# CFD.net
KiCad netlist of a schematic drawn in Altium Designer
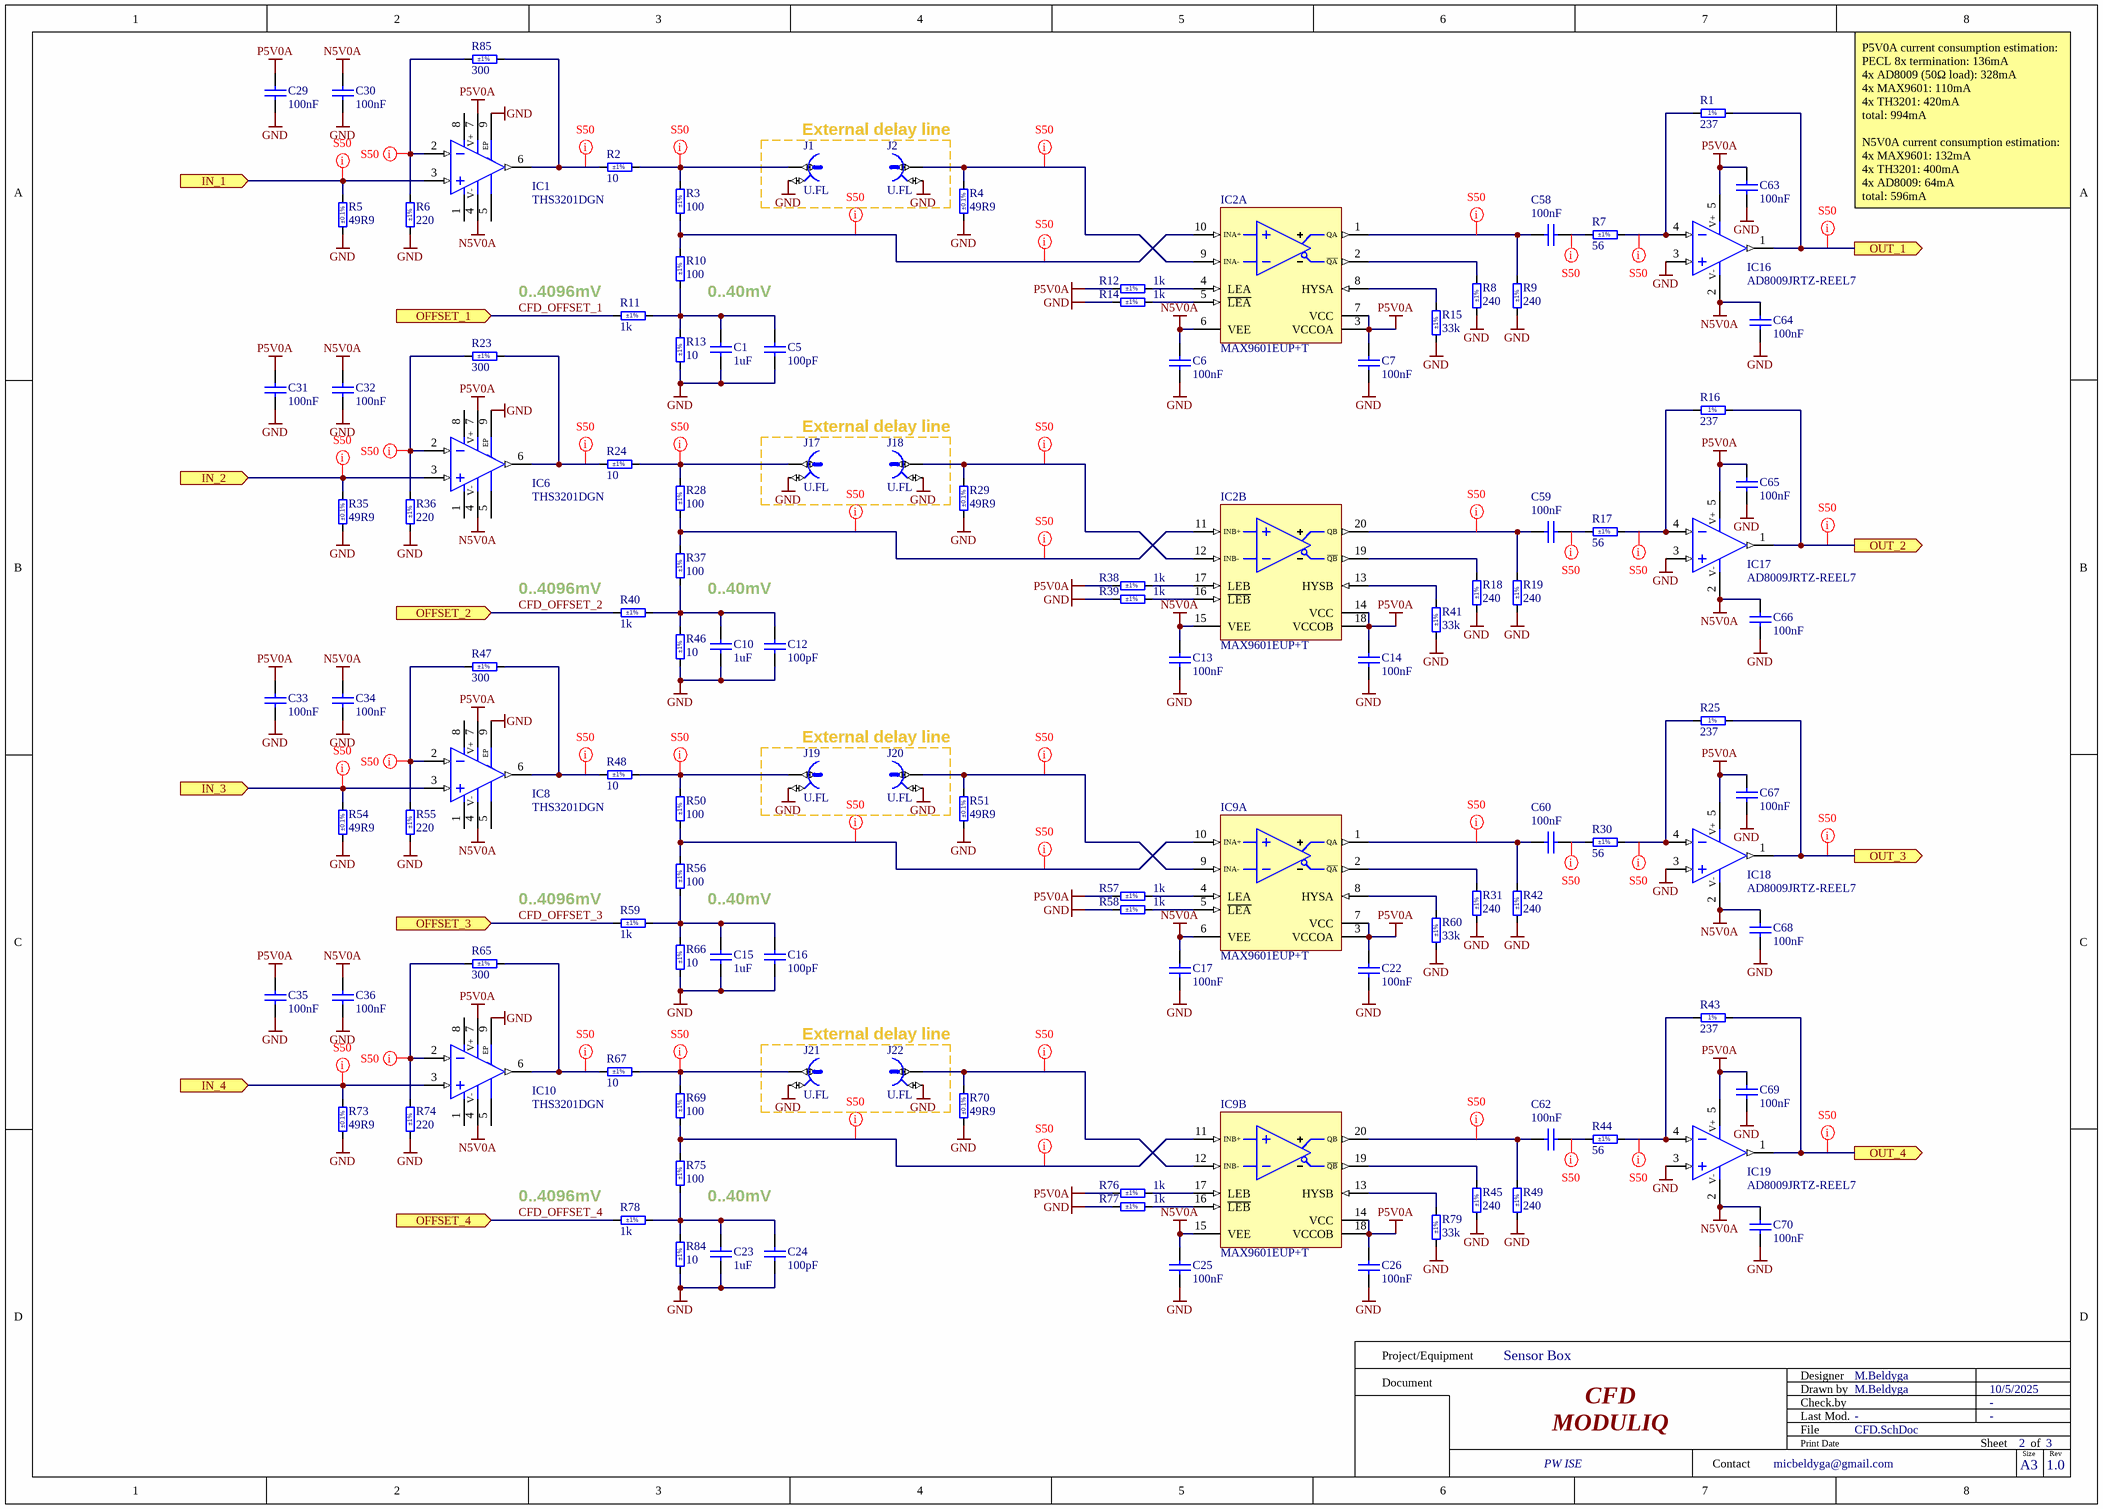
[diagram p0: CFD.SchDoc]

(export (version "E")
  (design (tool "Eeschema 10.0.6"))
  (components
    (comp (ref "C1")
      (value "1uF")
      (footprint "CAPC1005X55N")
      (description "Non-polarised capacitor")
      (fields
        (field (name "PART NUMBER") "CC0402_1UF_16V_10%_X5R")
        (field (name "VOLTAGE") "16V")
        (field (name "AUTHOR") "CERN DEM JLC")
      )
      (libsource (lib "Capacitors") (part "Capacitor - non polarized"))
    )
    (comp (ref "C5")
      (value "100pF")
      (footprint "CAPC1005X55N")
      (description "Non-polarised capacitor")
      (fields
        (field (name "PART NUMBER") "CC0402_100PF_25V_1%_C0G")
        (field (name "VOLTAGE") "25V")
        (field (name "AUTHOR") "CERN DEM HF")
      )
      (libsource (lib "Capacitors") (part "Capacitor - non polarized"))
    )
    (comp (ref "C6")
      (value "100nF")
      (footprint "CAPC1005X55N")
      (description "Non-polarised capacitor")
      (fields
        (field (name "PART NUMBER") "CC0402_100NF_50V_10%_X7R")
        (field (name "VOLTAGE") "50V")
        (field (name "AUTHOR") "CERN DEM MR")
      )
      (libsource (lib "Capacitors") (part "Capacitor - non polarized"))
    )
    (comp (ref "C7")
      (value "100nF")
      (footprint "CAPC1005X55N")
      (description "Non-polarised capacitor")
      (fields
        (field (name "PART NUMBER") "CC0402_100NF_50V_10%_X7R")
        (field (name "VOLTAGE") "50V")
        (field (name "AUTHOR") "CERN DEM MR")
      )
      (libsource (lib "Capacitors") (part "Capacitor - non polarized"))
    )
    (comp (ref "C10")
      (value "1uF")
      (footprint "CAPC1005X55N")
      (description "Non-polarised capacitor")
      (fields
        (field (name "PART NUMBER") "CC0402_1UF_16V_10%_X5R")
        (field (name "VOLTAGE") "16V")
        (field (name "AUTHOR") "CERN DEM JLC")
      )
      (libsource (lib "Capacitors") (part "Capacitor - non polarized"))
    )
    (comp (ref "C12")
      (value "100pF")
      (footprint "CAPC1005X55N")
      (description "Non-polarised capacitor")
      (fields
        (field (name "PART NUMBER") "CC0402_100PF_25V_1%_C0G")
        (field (name "VOLTAGE") "25V")
        (field (name "AUTHOR") "CERN DEM HF")
      )
      (libsource (lib "Capacitors") (part "Capacitor - non polarized"))
    )
    (comp (ref "C13")
      (value "100nF")
      (footprint "CAPC1005X55N")
      (description "Non-polarised capacitor")
      (fields
        (field (name "PART NUMBER") "CC0402_100NF_50V_10%_X7R")
        (field (name "VOLTAGE") "50V")
        (field (name "AUTHOR") "CERN DEM MR")
      )
      (libsource (lib "Capacitors") (part "Capacitor - non polarized"))
    )
    (comp (ref "C14")
      (value "100nF")
      (footprint "CAPC1005X55N")
      (description "Non-polarised capacitor")
      (fields
        (field (name "PART NUMBER") "CC0402_100NF_50V_10%_X7R")
        (field (name "VOLTAGE") "50V")
        (field (name "AUTHOR") "CERN DEM MR")
      )
      (libsource (lib "Capacitors") (part "Capacitor - non polarized"))
    )
    (comp (ref "C15")
      (value "1uF")
      (footprint "CAPC1005X55N")
      (description "Non-polarised capacitor")
      (fields
        (field (name "PART NUMBER") "CC0402_1UF_16V_10%_X5R")
        (field (name "VOLTAGE") "16V")
        (field (name "AUTHOR") "CERN DEM JLC")
      )
      (libsource (lib "Capacitors") (part "Capacitor - non polarized"))
    )
    (comp (ref "C16")
      (value "100pF")
      (footprint "CAPC1005X55N")
      (description "Non-polarised capacitor")
      (fields
        (field (name "PART NUMBER") "CC0402_100PF_25V_1%_C0G")
        (field (name "VOLTAGE") "25V")
        (field (name "AUTHOR") "CERN DEM HF")
      )
      (libsource (lib "Capacitors") (part "Capacitor - non polarized"))
    )
    (comp (ref "C17")
      (value "100nF")
      (footprint "CAPC1005X55N")
      (description "Non-polarised capacitor")
      (fields
        (field (name "PART NUMBER") "CC0402_100NF_50V_10%_X7R")
        (field (name "VOLTAGE") "50V")
        (field (name "AUTHOR") "CERN DEM MR")
      )
      (libsource (lib "Capacitors") (part "Capacitor - non polarized"))
    )
    (comp (ref "C22")
      (value "100nF")
      (footprint "CAPC1005X55N")
      (description "Non-polarised capacitor")
      (fields
        (field (name "PART NUMBER") "CC0402_100NF_50V_10%_X7R")
        (field (name "VOLTAGE") "50V")
        (field (name "AUTHOR") "CERN DEM MR")
      )
      (libsource (lib "Capacitors") (part "Capacitor - non polarized"))
    )
    (comp (ref "C23")
      (value "1uF")
      (footprint "CAPC1005X55N")
      (description "Non-polarised capacitor")
      (fields
        (field (name "PART NUMBER") "CC0402_1UF_16V_10%_X5R")
        (field (name "VOLTAGE") "16V")
        (field (name "AUTHOR") "CERN DEM JLC")
      )
      (libsource (lib "Capacitors") (part "Capacitor - non polarized"))
    )
    (comp (ref "C24")
      (value "100pF")
      (footprint "CAPC1005X55N")
      (description "Non-polarised capacitor")
      (fields
        (field (name "PART NUMBER") "CC0402_100PF_25V_1%_C0G")
        (field (name "VOLTAGE") "25V")
        (field (name "AUTHOR") "CERN DEM HF")
      )
      (libsource (lib "Capacitors") (part "Capacitor - non polarized"))
    )
    (comp (ref "C25")
      (value "100nF")
      (footprint "CAPC1005X55N")
      (description "Non-polarised capacitor")
      (fields
        (field (name "PART NUMBER") "CC0402_100NF_50V_10%_X7R")
        (field (name "VOLTAGE") "50V")
        (field (name "AUTHOR") "CERN DEM MR")
      )
      (libsource (lib "Capacitors") (part "Capacitor - non polarized"))
    )
    (comp (ref "C26")
      (value "100nF")
      (footprint "CAPC1005X55N")
      (description "Non-polarised capacitor")
      (fields
        (field (name "PART NUMBER") "CC0402_100NF_50V_10%_X7R")
        (field (name "VOLTAGE") "50V")
        (field (name "AUTHOR") "CERN DEM MR")
      )
      (libsource (lib "Capacitors") (part "Capacitor - non polarized"))
    )
    (comp (ref "C29")
      (value "100nF")
      (footprint "CAPC1005X55N")
      (description "Non-polarised capacitor")
      (fields
        (field (name "PART NUMBER") "CC0402_100NF_50V_10%_X7R")
        (field (name "VOLTAGE") "50V")
        (field (name "AUTHOR") "CERN DEM MR")
      )
      (libsource (lib "Capacitors") (part "Capacitor - non polarized"))
    )
    (comp (ref "C30")
      (value "100nF")
      (footprint "CAPC1005X55N")
      (description "Non-polarised capacitor")
      (fields
        (field (name "PART NUMBER") "CC0402_100NF_50V_10%_X7R")
        (field (name "VOLTAGE") "50V")
        (field (name "AUTHOR") "CERN DEM MR")
      )
      (libsource (lib "Capacitors") (part "Capacitor - non polarized"))
    )
    (comp (ref "C31")
      (value "100nF")
      (footprint "CAPC1005X55N")
      (description "Non-polarised capacitor")
      (fields
        (field (name "PART NUMBER") "CC0402_100NF_50V_10%_X7R")
        (field (name "VOLTAGE") "50V")
        (field (name "AUTHOR") "CERN DEM MR")
      )
      (libsource (lib "Capacitors") (part "Capacitor - non polarized"))
    )
    (comp (ref "C32")
      (value "100nF")
      (footprint "CAPC1005X55N")
      (description "Non-polarised capacitor")
      (fields
        (field (name "PART NUMBER") "CC0402_100NF_50V_10%_X7R")
        (field (name "VOLTAGE") "50V")
        (field (name "AUTHOR") "CERN DEM MR")
      )
      (libsource (lib "Capacitors") (part "Capacitor - non polarized"))
    )
    (comp (ref "C33")
      (value "100nF")
      (footprint "CAPC1005X55N")
      (description "Non-polarised capacitor")
      (fields
        (field (name "PART NUMBER") "CC0402_100NF_50V_10%_X7R")
        (field (name "VOLTAGE") "50V")
        (field (name "AUTHOR") "CERN DEM MR")
      )
      (libsource (lib "Capacitors") (part "Capacitor - non polarized"))
    )
    (comp (ref "C34")
      (value "100nF")
      (footprint "CAPC1005X55N")
      (description "Non-polarised capacitor")
      (fields
        (field (name "PART NUMBER") "CC0402_100NF_50V_10%_X7R")
        (field (name "VOLTAGE") "50V")
        (field (name "AUTHOR") "CERN DEM MR")
      )
      (libsource (lib "Capacitors") (part "Capacitor - non polarized"))
    )
    (comp (ref "C35")
      (value "100nF")
      (footprint "CAPC1005X55N")
      (description "Non-polarised capacitor")
      (fields
        (field (name "PART NUMBER") "CC0402_100NF_50V_10%_X7R")
        (field (name "VOLTAGE") "50V")
        (field (name "AUTHOR") "CERN DEM MR")
      )
      (libsource (lib "Capacitors") (part "Capacitor - non polarized"))
    )
    (comp (ref "C36")
      (value "100nF")
      (footprint "CAPC1005X55N")
      (description "Non-polarised capacitor")
      (fields
        (field (name "PART NUMBER") "CC0402_100NF_50V_10%_X7R")
        (field (name "VOLTAGE") "50V")
        (field (name "AUTHOR") "CERN DEM MR")
      )
      (libsource (lib "Capacitors") (part "Capacitor - non polarized"))
    )
    (comp (ref "C58")
      (value "100nF")
      (footprint "CAPC1005X55N")
      (description "Non-polarised capacitor")
      (fields
        (field (name "PART NUMBER") "CC0402_100NF_50V_10%_X7R")
        (field (name "VOLTAGE") "50V")
        (field (name "AUTHOR") "CERN DEM MR")
      )
      (libsource (lib "Capacitors") (part "Capacitor - non polarized"))
    )
    (comp (ref "C59")
      (value "100nF")
      (footprint "CAPC1005X55N")
      (description "Non-polarised capacitor")
      (fields
        (field (name "PART NUMBER") "CC0402_100NF_50V_10%_X7R")
        (field (name "VOLTAGE") "50V")
        (field (name "AUTHOR") "CERN DEM MR")
      )
      (libsource (lib "Capacitors") (part "Capacitor - non polarized"))
    )
    (comp (ref "C60")
      (value "100nF")
      (footprint "CAPC1005X55N")
      (description "Non-polarised capacitor")
      (fields
        (field (name "PART NUMBER") "CC0402_100NF_50V_10%_X7R")
        (field (name "VOLTAGE") "50V")
        (field (name "AUTHOR") "CERN DEM MR")
      )
      (libsource (lib "Capacitors") (part "Capacitor - non polarized"))
    )
    (comp (ref "C62")
      (value "100nF")
      (footprint "CAPC1005X55N")
      (description "Non-polarised capacitor")
      (fields
        (field (name "PART NUMBER") "CC0402_100NF_50V_10%_X7R")
        (field (name "VOLTAGE") "50V")
        (field (name "AUTHOR") "CERN DEM MR")
      )
      (libsource (lib "Capacitors") (part "Capacitor - non polarized"))
    )
    (comp (ref "C63")
      (value "100nF")
      (footprint "CAPC1005X55N")
      (description "Non-polarised capacitor")
      (fields
        (field (name "PART NUMBER") "CC0402_100NF_50V_10%_X7R")
        (field (name "VOLTAGE") "50V")
        (field (name "AUTHOR") "CERN DEM MR")
      )
      (libsource (lib "Capacitors") (part "Capacitor - non polarized"))
    )
    (comp (ref "C64")
      (value "100nF")
      (footprint "CAPC1005X55N")
      (description "Non-polarised capacitor")
      (fields
        (field (name "PART NUMBER") "CC0402_100NF_50V_10%_X7R")
        (field (name "VOLTAGE") "50V")
        (field (name "AUTHOR") "CERN DEM MR")
      )
      (libsource (lib "Capacitors") (part "Capacitor - non polarized"))
    )
    (comp (ref "C65")
      (value "100nF")
      (footprint "CAPC1005X55N")
      (description "Non-polarised capacitor")
      (fields
        (field (name "PART NUMBER") "CC0402_100NF_50V_10%_X7R")
        (field (name "VOLTAGE") "50V")
        (field (name "AUTHOR") "CERN DEM MR")
      )
      (libsource (lib "Capacitors") (part "Capacitor - non polarized"))
    )
    (comp (ref "C66")
      (value "100nF")
      (footprint "CAPC1005X55N")
      (description "Non-polarised capacitor")
      (fields
        (field (name "PART NUMBER") "CC0402_100NF_50V_10%_X7R")
        (field (name "VOLTAGE") "50V")
        (field (name "AUTHOR") "CERN DEM MR")
      )
      (libsource (lib "Capacitors") (part "Capacitor - non polarized"))
    )
    (comp (ref "C67")
      (value "100nF")
      (footprint "CAPC1005X55N")
      (description "Non-polarised capacitor")
      (fields
        (field (name "PART NUMBER") "CC0402_100NF_50V_10%_X7R")
        (field (name "VOLTAGE") "50V")
        (field (name "AUTHOR") "CERN DEM MR")
      )
      (libsource (lib "Capacitors") (part "Capacitor - non polarized"))
    )
    (comp (ref "C68")
      (value "100nF")
      (footprint "CAPC1005X55N")
      (description "Non-polarised capacitor")
      (fields
        (field (name "PART NUMBER") "CC0402_100NF_50V_10%_X7R")
        (field (name "VOLTAGE") "50V")
        (field (name "AUTHOR") "CERN DEM MR")
      )
      (libsource (lib "Capacitors") (part "Capacitor - non polarized"))
    )
    (comp (ref "C69")
      (value "100nF")
      (footprint "CAPC1005X55N")
      (description "Non-polarised capacitor")
      (fields
        (field (name "PART NUMBER") "CC0402_100NF_50V_10%_X7R")
        (field (name "VOLTAGE") "50V")
        (field (name "AUTHOR") "CERN DEM MR")
      )
      (libsource (lib "Capacitors") (part "Capacitor - non polarized"))
    )
    (comp (ref "C70")
      (value "100nF")
      (footprint "CAPC1005X55N")
      (description "Non-polarised capacitor")
      (fields
        (field (name "PART NUMBER") "CC0402_100NF_50V_10%_X7R")
        (field (name "VOLTAGE") "50V")
        (field (name "AUTHOR") "CERN DEM MR")
      )
      (libsource (lib "Capacitors") (part "Capacitor - non polarized"))
    )
    (comp (ref "IC1")
      (value "THS3201DGN")
      (footprint "SOP65P490X110-9N-R152X190")
      (description "Operational Amplifier with Exposed Thermal Pad")
      (fields (field (name "MANUFACTURER") "TEXAS INSTRUMENTS") (field (name "AUTHOR") "CERN DEM JLC"))
      (libsource (lib "ICs And Semiconductors") (part "Operational Amplifier Type5 + Exposed Pad"))
    )
    (comp (ref "IC2")
      (value "MAX9601EUP+T")
      (footprint "SOP65P640X120-20N")
      (description "Dual ECL and Dual/Quad PECL, 500ps, Ultra-High-Speed Comparators")
      (fields (field (name "MANUFACTURER") "Analog Devices"))
      (libsource (lib "mb") (part "MAX9601EUP+T"))
    )
    (comp (ref "IC6")
      (value "THS3201DGN")
      (footprint "SOP65P490X110-9N-R152X190")
      (description "Operational Amplifier with Exposed Thermal Pad")
      (fields (field (name "MANUFACTURER") "TEXAS INSTRUMENTS") (field (name "AUTHOR") "CERN DEM JLC"))
      (libsource (lib "ICs And Semiconductors") (part "Operational Amplifier Type5 + Exposed Pad"))
    )
    (comp (ref "IC8")
      (value "THS3201DGN")
      (footprint "SOP65P490X110-9N-R152X190")
      (description "Operational Amplifier with Exposed Thermal Pad")
      (fields (field (name "MANUFACTURER") "TEXAS INSTRUMENTS") (field (name "AUTHOR") "CERN DEM JLC"))
      (libsource (lib "ICs And Semiconductors") (part "Operational Amplifier Type5 + Exposed Pad"))
    )
    (comp (ref "IC9")
      (value "MAX9601EUP+T")
      (footprint "SOP65P640X120-20N")
      (description "Dual ECL and Dual/Quad PECL, 500ps, Ultra-High-Speed Comparators")
      (fields (field (name "MANUFACTURER") "Analog Devices"))
      (libsource (lib "mb") (part "MAX9601EUP+T"))
    )
    (comp (ref "IC10")
      (value "THS3201DGN")
      (footprint "SOP65P490X110-9N-R152X190")
      (description "Operational Amplifier with Exposed Thermal Pad")
      (fields (field (name "MANUFACTURER") "TEXAS INSTRUMENTS") (field (name "AUTHOR") "CERN DEM JLC"))
      (libsource (lib "ICs And Semiconductors") (part "Operational Amplifier Type5 + Exposed Pad"))
    )
    (comp (ref "IC16")
      (value "AD8009JRTZ-REEL7")
      (footprint "SOT95P280X145-5N")
      (description "Operational Amplifier")
      (fields
        (field (name "MANUFACTURER") "ANALOG DEVICES")
        (field (name "MANUFACTURER PART NUMBER") "AD8009JRT")
        (field (name "AUTHOR") "CERN DEM JLC")
      )
      (libsource (lib "ICs And Semiconductors") (part "Operational Amplifier Type7"))
    )
    (comp (ref "IC17")
      (value "AD8009JRTZ-REEL7")
      (footprint "SOT95P280X145-5N")
      (description "Operational Amplifier")
      (fields
        (field (name "MANUFACTURER") "ANALOG DEVICES")
        (field (name "MANUFACTURER PART NUMBER") "AD8009JRT")
        (field (name "AUTHOR") "CERN DEM JLC")
      )
      (libsource (lib "ICs And Semiconductors") (part "Operational Amplifier Type7"))
    )
    (comp (ref "IC18")
      (value "AD8009JRTZ-REEL7")
      (footprint "SOT95P280X145-5N")
      (description "Operational Amplifier")
      (fields
        (field (name "MANUFACTURER") "ANALOG DEVICES")
        (field (name "MANUFACTURER PART NUMBER") "AD8009JRT")
        (field (name "AUTHOR") "CERN DEM JLC")
      )
      (libsource (lib "ICs And Semiconductors") (part "Operational Amplifier Type7"))
    )
    (comp (ref "IC19")
      (value "AD8009JRTZ-REEL7")
      (footprint "SOT95P280X145-5N")
      (description "Operational Amplifier")
      (fields
        (field (name "MANUFACTURER") "ANALOG DEVICES")
        (field (name "MANUFACTURER PART NUMBER") "AD8009JRT")
        (field (name "AUTHOR") "CERN DEM JLC")
      )
      (libsource (lib "ICs And Semiconductors") (part "Operational Amplifier Type7"))
    )
    (comp (ref "J1")
      (value "U.FL")
      (footprint "HIROSE_U.FL-R-SMT-1")
      (fields
        (field (name "PART NUMBER") "HIROSE_U.FL-R-SMT-1(10)")
        (field (name "MANUFACTURER") "HIROSE (HRS)")
        (field (name "MANUFACTURER PART NUMBER") "U.FL-R-SMT-1")
        (field (name "AUTHOR") "CERN DEM JLC")
      )
      (libsource (lib "") (part "Coax_1Male_1Shield_1"))
    )
    (comp (ref "J2")
      (value "U.FL")
      (footprint "HIROSE_U.FL-R-SMT-1")
      (fields
        (field (name "PART NUMBER") "HIROSE_U.FL-R-SMT-1(10)")
        (field (name "MANUFACTURER") "HIROSE (HRS)")
        (field (name "MANUFACTURER PART NUMBER") "U.FL-R-SMT-1")
        (field (name "AUTHOR") "CERN DEM JLC")
      )
      (libsource (lib "Connectors") (part "Coax_1Male_1Shield"))
    )
    (comp (ref "J17")
      (value "U.FL")
      (footprint "HIROSE_U.FL-R-SMT-1")
      (fields
        (field (name "PART NUMBER") "HIROSE_U.FL-R-SMT-1(10)")
        (field (name "MANUFACTURER") "HIROSE (HRS)")
        (field (name "MANUFACTURER PART NUMBER") "U.FL-R-SMT-1")
        (field (name "AUTHOR") "CERN DEM JLC")
      )
      (libsource (lib "") (part "Coax_1Male_1Shield_1"))
    )
    (comp (ref "J18")
      (value "U.FL")
      (footprint "HIROSE_U.FL-R-SMT-1")
      (fields
        (field (name "PART NUMBER") "HIROSE_U.FL-R-SMT-1(10)")
        (field (name "MANUFACTURER") "HIROSE (HRS)")
        (field (name "MANUFACTURER PART NUMBER") "U.FL-R-SMT-1")
        (field (name "AUTHOR") "CERN DEM JLC")
      )
      (libsource (lib "Connectors") (part "Coax_1Male_1Shield"))
    )
    (comp (ref "J19")
      (value "U.FL")
      (footprint "HIROSE_U.FL-R-SMT-1")
      (fields
        (field (name "PART NUMBER") "HIROSE_U.FL-R-SMT-1(10)")
        (field (name "MANUFACTURER") "HIROSE (HRS)")
        (field (name "MANUFACTURER PART NUMBER") "U.FL-R-SMT-1")
        (field (name "AUTHOR") "CERN DEM JLC")
      )
      (libsource (lib "") (part "Coax_1Male_1Shield_1"))
    )
    (comp (ref "J20")
      (value "U.FL")
      (footprint "HIROSE_U.FL-R-SMT-1")
      (fields
        (field (name "PART NUMBER") "HIROSE_U.FL-R-SMT-1(10)")
        (field (name "MANUFACTURER") "HIROSE (HRS)")
        (field (name "MANUFACTURER PART NUMBER") "U.FL-R-SMT-1")
        (field (name "AUTHOR") "CERN DEM JLC")
      )
      (libsource (lib "Connectors") (part "Coax_1Male_1Shield"))
    )
    (comp (ref "J21")
      (value "U.FL")
      (footprint "HIROSE_U.FL-R-SMT-1")
      (fields
        (field (name "PART NUMBER") "HIROSE_U.FL-R-SMT-1(10)")
        (field (name "MANUFACTURER") "HIROSE (HRS)")
        (field (name "MANUFACTURER PART NUMBER") "U.FL-R-SMT-1")
        (field (name "AUTHOR") "CERN DEM JLC")
      )
      (libsource (lib "") (part "Coax_1Male_1Shield_1"))
    )
    (comp (ref "J22")
      (value "U.FL")
      (footprint "HIROSE_U.FL-R-SMT-1")
      (fields
        (field (name "PART NUMBER") "HIROSE_U.FL-R-SMT-1(10)")
        (field (name "MANUFACTURER") "HIROSE (HRS)")
        (field (name "MANUFACTURER PART NUMBER") "U.FL-R-SMT-1")
        (field (name "AUTHOR") "CERN DEM JLC")
      )
      (libsource (lib "Connectors") (part "Coax_1Male_1Shield"))
    )
    (comp (ref "R1")
      (value "237")
      (footprint "RESC1005X40N")
      (description "RES 237 OHM 1% 1/16W 0402")
      (fields
        (field (name "PART NUMBER") "R0402_237R_1%_0.0625W")
        (field (name "POWER") "0.0625W")
        (field (name "AUTHOR") "Michal Beldyga")
      )
      (libsource (lib "") (part "Resistor - 1%_1"))
    )
    (comp (ref "R2")
      (value "10")
      (footprint "RESC1005X40N")
      (description "Resistor - 1%")
      (fields
        (field (name "TOLERANCE") "±1%")
        (field (name "PART NUMBER") "R0402_10R_1%_0.0625W_200PPM")
        (field (name "POWER") "0.0625W")
        (field (name "AUTHOR") "CERN DEM JLC")
      )
      (libsource (lib "Resistors") (part "Resistor - 1%"))
    )
    (comp (ref "R3")
      (value "100")
      (footprint "RESC1005X40N")
      (description "Resistor - 1%")
      (fields
        (field (name "TOLERANCE") "±1%")
        (field (name "PART NUMBER") "R0402_100R_1%_0.0625W_100PPM")
        (field (name "POWER") "0.0625W")
        (field (name "AUTHOR") "CERN DEM JLC")
      )
      (libsource (lib "Resistors") (part "Resistor - 1%"))
    )
    (comp (ref "R4")
      (value "49R9")
      (footprint "RESC2012X60N")
      (description "Resistor - 0.1%")
      (fields
        (field (name "TOLERANCE") "±0.1%")
        (field (name "PART NUMBER") "R0805_49R9_0.1%_0.1W_10PPM")
        (field (name "POWER") "0.1W")
        (field (name "AUTHOR") "CERN DEM JLC")
      )
      (libsource (lib "Resistors") (part "Resistor - 0.1%"))
    )
    (comp (ref "R5")
      (value "49R9")
      (footprint "RESC2012X60N")
      (description "Resistor - 0.1%")
      (fields
        (field (name "TOLERANCE") "±0.1%")
        (field (name "PART NUMBER") "R0805_49R9_0.1%_0.1W_10PPM")
        (field (name "POWER") "0.1W")
        (field (name "AUTHOR") "CERN DEM JLC")
      )
      (libsource (lib "Resistors") (part "Resistor - 0.1%"))
    )
    (comp (ref "R6")
      (value "220")
      (footprint "RESC1005X40N")
      (description "Resistor - 1%")
      (fields
        (field (name "TOLERANCE") "±1%")
        (field (name "PART NUMBER") "R0402_220R_1%_0.0625W_100PPM")
        (field (name "POWER") "0.0625W")
        (field (name "AUTHOR") "CERN DEM JLC")
      )
      (libsource (lib "Resistors") (part "Resistor - 1%"))
    )
    (comp (ref "R7")
      (value "56")
      (footprint "RESC1005X40N")
      (description "Resistor - 1%")
      (fields
        (field (name "TOLERANCE") "±1%")
        (field (name "PART NUMBER") "R0402_56R_1%_0.0625W_100PPM")
        (field (name "POWER") "0.0625W")
        (field (name "AUTHOR") "CERN DEM JLC")
      )
      (libsource (lib "Resistors") (part "Resistor - 1%"))
    )
    (comp (ref "R8")
      (value "240")
      (footprint "RESC1608X55N")
      (description "Resistor - 1%")
      (fields
        (field (name "TOLERANCE") "±1%")
        (field (name "PART NUMBER") "R0603_240R_1%_0.1W_100PPM")
        (field (name "POWER") "0.1W")
        (field (name "AUTHOR") "CERN DEM JLC")
      )
      (libsource (lib "Resistors") (part "Resistor - 1%"))
    )
    (comp (ref "R9")
      (value "240")
      (footprint "RESC1608X55N")
      (description "Resistor - 1%")
      (fields
        (field (name "TOLERANCE") "±1%")
        (field (name "PART NUMBER") "R0603_240R_1%_0.1W_100PPM")
        (field (name "POWER") "0.1W")
        (field (name "AUTHOR") "CERN DEM JLC")
      )
      (libsource (lib "Resistors") (part "Resistor - 1%"))
    )
    (comp (ref "R10")
      (value "100")
      (footprint "RESC1005X40N")
      (description "Resistor - 1%")
      (fields
        (field (name "TOLERANCE") "±1%")
        (field (name "PART NUMBER") "R0402_100R_1%_0.0625W_100PPM")
        (field (name "POWER") "0.0625W")
        (field (name "AUTHOR") "CERN DEM JLC")
      )
      (libsource (lib "Resistors") (part "Resistor - 1%"))
    )
    (comp (ref "R11")
      (value "1k")
      (footprint "RESC1005X40N")
      (description "Resistor - 1%")
      (fields
        (field (name "TOLERANCE") "±1%")
        (field (name "PART NUMBER") "R0402_1K_1%_0.0625W_100PPM")
        (field (name "POWER") "0.0625W")
        (field (name "AUTHOR") "CERN DEM JLC")
      )
      (libsource (lib "Resistors") (part "Resistor - 1%"))
    )
    (comp (ref "R12")
      (value "1k")
      (footprint "RESC1005X40N")
      (description "Resistor - 1%")
      (fields
        (field (name "TOLERANCE") "±1%")
        (field (name "PART NUMBER") "R0402_1K_1%_0.0625W_100PPM")
        (field (name "POWER") "0.0625W")
        (field (name "AUTHOR") "CERN DEM JLC")
      )
      (libsource (lib "Resistors") (part "Resistor - 1%"))
    )
    (comp (ref "R13")
      (value "10")
      (footprint "RESC1005X40N")
      (description "Resistor - 1%")
      (fields
        (field (name "TOLERANCE") "±1%")
        (field (name "PART NUMBER") "R0402_10R_1%_0.0625W_200PPM")
        (field (name "POWER") "0.0625W")
        (field (name "AUTHOR") "CERN DEM JLC")
      )
      (libsource (lib "Resistors") (part "Resistor - 1%"))
    )
    (comp (ref "R14")
      (value "1k")
      (footprint "RESC1005X40N")
      (description "Resistor - 1%")
      (fields
        (field (name "TOLERANCE") "±1%")
        (field (name "PART NUMBER") "R0402_1K_1%_0.0625W_100PPM")
        (field (name "POWER") "0.0625W")
        (field (name "AUTHOR") "CERN DEM JLC")
      )
      (libsource (lib "Resistors") (part "Resistor - 1%"))
    )
    (comp (ref "R15")
      (value "33k")
      (footprint "RESC1005X40N")
      (description "Resistor - 1%")
      (fields
        (field (name "TOLERANCE") "±1%")
        (field (name "PART NUMBER") "R0402_33K_1%_0.0625W_100PPM")
        (field (name "POWER") "0.0625W")
        (field (name "AUTHOR") "CERN DEM JLC")
      )
      (libsource (lib "Resistors") (part "Resistor - 1%"))
    )
    (comp (ref "R16")
      (value "237")
      (footprint "RESC1005X40N")
      (description "RES 237 OHM 1% 1/16W 0402")
      (fields
        (field (name "PART NUMBER") "R0402_237R_1%_0.0625W")
        (field (name "POWER") "0.0625W")
        (field (name "AUTHOR") "Michal Beldyga")
      )
      (libsource (lib "") (part "Resistor - 1%_1"))
    )
    (comp (ref "R17")
      (value "56")
      (footprint "RESC1005X40N")
      (description "Resistor - 1%")
      (fields
        (field (name "TOLERANCE") "±1%")
        (field (name "PART NUMBER") "R0402_56R_1%_0.0625W_100PPM")
        (field (name "POWER") "0.0625W")
        (field (name "AUTHOR") "CERN DEM JLC")
      )
      (libsource (lib "Resistors") (part "Resistor - 1%"))
    )
    (comp (ref "R18")
      (value "240")
      (footprint "RESC1608X55N")
      (description "Resistor - 1%")
      (fields
        (field (name "TOLERANCE") "±1%")
        (field (name "PART NUMBER") "R0603_240R_1%_0.1W_100PPM")
        (field (name "POWER") "0.1W")
        (field (name "AUTHOR") "CERN DEM JLC")
      )
      (libsource (lib "Resistors") (part "Resistor - 1%"))
    )
    (comp (ref "R19")
      (value "240")
      (footprint "RESC1608X55N")
      (description "Resistor - 1%")
      (fields
        (field (name "TOLERANCE") "±1%")
        (field (name "PART NUMBER") "R0603_240R_1%_0.1W_100PPM")
        (field (name "POWER") "0.1W")
        (field (name "AUTHOR") "CERN DEM JLC")
      )
      (libsource (lib "Resistors") (part "Resistor - 1%"))
    )
    (comp (ref "R23")
      (value "300")
      (footprint "RESC1005X40N")
      (description "Resistor - 1%")
      (fields
        (field (name "TOLERANCE") "±1%")
        (field (name "PART NUMBER") "R0402_300R_1%_0.0625W_100PPM")
        (field (name "POWER") "0.0625W")
        (field (name "AUTHOR") "CERN DEM JLC")
      )
      (libsource (lib "Resistors") (part "Resistor - 1%"))
    )
    (comp (ref "R24")
      (value "10")
      (footprint "RESC1005X40N")
      (description "Resistor - 1%")
      (fields
        (field (name "TOLERANCE") "±1%")
        (field (name "PART NUMBER") "R0402_10R_1%_0.0625W_200PPM")
        (field (name "POWER") "0.0625W")
        (field (name "AUTHOR") "CERN DEM JLC")
      )
      (libsource (lib "Resistors") (part "Resistor - 1%"))
    )
    (comp (ref "R25")
      (value "237")
      (footprint "RESC1005X40N")
      (description "RES 237 OHM 1% 1/16W 0402")
      (fields
        (field (name "PART NUMBER") "R0402_237R_1%_0.0625W")
        (field (name "POWER") "0.0625W")
        (field (name "AUTHOR") "Michal Beldyga")
      )
      (libsource (lib "") (part "Resistor - 1%_1"))
    )
    (comp (ref "R28")
      (value "100")
      (footprint "RESC1005X40N")
      (description "Resistor - 1%")
      (fields
        (field (name "TOLERANCE") "±1%")
        (field (name "PART NUMBER") "R0402_100R_1%_0.0625W_100PPM")
        (field (name "POWER") "0.0625W")
        (field (name "AUTHOR") "CERN DEM JLC")
      )
      (libsource (lib "Resistors") (part "Resistor - 1%"))
    )
    (comp (ref "R29")
      (value "49R9")
      (footprint "RESC2012X60N")
      (description "Resistor - 0.1%")
      (fields
        (field (name "TOLERANCE") "±0.1%")
        (field (name "PART NUMBER") "R0805_49R9_0.1%_0.1W_10PPM")
        (field (name "POWER") "0.1W")
        (field (name "AUTHOR") "CERN DEM JLC")
      )
      (libsource (lib "Resistors") (part "Resistor - 0.1%"))
    )
    (comp (ref "R30")
      (value "56")
      (footprint "RESC1005X40N")
      (description "Resistor - 1%")
      (fields
        (field (name "TOLERANCE") "±1%")
        (field (name "PART NUMBER") "R0402_56R_1%_0.0625W_100PPM")
        (field (name "POWER") "0.0625W")
        (field (name "AUTHOR") "CERN DEM JLC")
      )
      (libsource (lib "Resistors") (part "Resistor - 1%"))
    )
    (comp (ref "R31")
      (value "240")
      (footprint "RESC1608X55N")
      (description "Resistor - 1%")
      (fields
        (field (name "TOLERANCE") "±1%")
        (field (name "PART NUMBER") "R0603_240R_1%_0.1W_100PPM")
        (field (name "POWER") "0.1W")
        (field (name "AUTHOR") "CERN DEM JLC")
      )
      (libsource (lib "Resistors") (part "Resistor - 1%"))
    )
    (comp (ref "R35")
      (value "49R9")
      (footprint "RESC2012X60N")
      (description "Resistor - 0.1%")
      (fields
        (field (name "TOLERANCE") "±0.1%")
        (field (name "PART NUMBER") "R0805_49R9_0.1%_0.1W_10PPM")
        (field (name "POWER") "0.1W")
        (field (name "AUTHOR") "CERN DEM JLC")
      )
      (libsource (lib "Resistors") (part "Resistor - 0.1%"))
    )
    (comp (ref "R36")
      (value "220")
      (footprint "RESC1005X40N")
      (description "Resistor - 1%")
      (fields
        (field (name "TOLERANCE") "±1%")
        (field (name "PART NUMBER") "R0402_220R_1%_0.0625W_100PPM")
        (field (name "POWER") "0.0625W")
        (field (name "AUTHOR") "CERN DEM JLC")
      )
      (libsource (lib "Resistors") (part "Resistor - 1%"))
    )
    (comp (ref "R37")
      (value "100")
      (footprint "RESC1005X40N")
      (description "Resistor - 1%")
      (fields
        (field (name "TOLERANCE") "±1%")
        (field (name "PART NUMBER") "R0402_100R_1%_0.0625W_100PPM")
        (field (name "POWER") "0.0625W")
        (field (name "AUTHOR") "CERN DEM JLC")
      )
      (libsource (lib "Resistors") (part "Resistor - 1%"))
    )
    (comp (ref "R38")
      (value "1k")
      (footprint "RESC1005X40N")
      (description "Resistor - 1%")
      (fields
        (field (name "TOLERANCE") "±1%")
        (field (name "PART NUMBER") "R0402_1K_1%_0.0625W_100PPM")
        (field (name "POWER") "0.0625W")
        (field (name "AUTHOR") "CERN DEM JLC")
      )
      (libsource (lib "Resistors") (part "Resistor - 1%"))
    )
    (comp (ref "R39")
      (value "1k")
      (footprint "RESC1005X40N")
      (description "Resistor - 1%")
      (fields
        (field (name "TOLERANCE") "±1%")
        (field (name "PART NUMBER") "R0402_1K_1%_0.0625W_100PPM")
        (field (name "POWER") "0.0625W")
        (field (name "AUTHOR") "CERN DEM JLC")
      )
      (libsource (lib "Resistors") (part "Resistor - 1%"))
    )
    (comp (ref "R40")
      (value "1k")
      (footprint "RESC1005X40N")
      (description "Resistor - 1%")
      (fields
        (field (name "TOLERANCE") "±1%")
        (field (name "PART NUMBER") "R0402_1K_1%_0.0625W_100PPM")
        (field (name "POWER") "0.0625W")
        (field (name "AUTHOR") "CERN DEM JLC")
      )
      (libsource (lib "Resistors") (part "Resistor - 1%"))
    )
    (comp (ref "R41")
      (value "33k")
      (footprint "RESC1005X40N")
      (description "Resistor - 1%")
      (fields
        (field (name "TOLERANCE") "±1%")
        (field (name "PART NUMBER") "R0402_33K_1%_0.0625W_100PPM")
        (field (name "POWER") "0.0625W")
        (field (name "AUTHOR") "CERN DEM JLC")
      )
      (libsource (lib "Resistors") (part "Resistor - 1%"))
    )
    (comp (ref "R42")
      (value "240")
      (footprint "RESC1608X55N")
      (description "Resistor - 1%")
      (fields
        (field (name "TOLERANCE") "±1%")
        (field (name "PART NUMBER") "R0603_240R_1%_0.1W_100PPM")
        (field (name "POWER") "0.1W")
        (field (name "AUTHOR") "CERN DEM JLC")
      )
      (libsource (lib "Resistors") (part "Resistor - 1%"))
    )
    (comp (ref "R43")
      (value "237")
      (footprint "RESC1005X40N")
      (description "RES 237 OHM 1% 1/16W 0402")
      (fields
        (field (name "PART NUMBER") "R0402_237R_1%_0.0625W")
        (field (name "POWER") "0.0625W")
        (field (name "AUTHOR") "Michal Beldyga")
      )
      (libsource (lib "") (part "Resistor - 1%_1"))
    )
    (comp (ref "R44")
      (value "56")
      (footprint "RESC1005X40N")
      (description "Resistor - 1%")
      (fields
        (field (name "TOLERANCE") "±1%")
        (field (name "PART NUMBER") "R0402_56R_1%_0.0625W_100PPM")
        (field (name "POWER") "0.0625W")
        (field (name "AUTHOR") "CERN DEM JLC")
      )
      (libsource (lib "Resistors") (part "Resistor - 1%"))
    )
    (comp (ref "R45")
      (value "240")
      (footprint "RESC1608X55N")
      (description "Resistor - 1%")
      (fields
        (field (name "TOLERANCE") "±1%")
        (field (name "PART NUMBER") "R0603_240R_1%_0.1W_100PPM")
        (field (name "POWER") "0.1W")
        (field (name "AUTHOR") "CERN DEM JLC")
      )
      (libsource (lib "Resistors") (part "Resistor - 1%"))
    )
    (comp (ref "R46")
      (value "10")
      (footprint "RESC1005X40N")
      (description "Resistor - 1%")
      (fields
        (field (name "TOLERANCE") "±1%")
        (field (name "PART NUMBER") "R0402_10R_1%_0.0625W_200PPM")
        (field (name "POWER") "0.0625W")
        (field (name "AUTHOR") "CERN DEM JLC")
      )
      (libsource (lib "Resistors") (part "Resistor - 1%"))
    )
    (comp (ref "R47")
      (value "300")
      (footprint "RESC1005X40N")
      (description "Resistor - 1%")
      (fields
        (field (name "TOLERANCE") "±1%")
        (field (name "PART NUMBER") "R0402_300R_1%_0.0625W_100PPM")
        (field (name "POWER") "0.0625W")
        (field (name "AUTHOR") "CERN DEM JLC")
      )
      (libsource (lib "Resistors") (part "Resistor - 1%"))
    )
    (comp (ref "R48")
      (value "10")
      (footprint "RESC1005X40N")
      (description "Resistor - 1%")
      (fields
        (field (name "TOLERANCE") "±1%")
        (field (name "PART NUMBER") "R0402_10R_1%_0.0625W_200PPM")
        (field (name "POWER") "0.0625W")
        (field (name "AUTHOR") "CERN DEM JLC")
      )
      (libsource (lib "Resistors") (part "Resistor - 1%"))
    )
    (comp (ref "R49")
      (value "240")
      (footprint "RESC1608X55N")
      (description "Resistor - 1%")
      (fields
        (field (name "TOLERANCE") "±1%")
        (field (name "PART NUMBER") "R0603_240R_1%_0.1W_100PPM")
        (field (name "POWER") "0.1W")
        (field (name "AUTHOR") "CERN DEM JLC")
      )
      (libsource (lib "Resistors") (part "Resistor - 1%"))
    )
    (comp (ref "R50")
      (value "100")
      (footprint "RESC1005X40N")
      (description "Resistor - 1%")
      (fields
        (field (name "TOLERANCE") "±1%")
        (field (name "PART NUMBER") "R0402_100R_1%_0.0625W_100PPM")
        (field (name "POWER") "0.0625W")
        (field (name "AUTHOR") "CERN DEM JLC")
      )
      (libsource (lib "Resistors") (part "Resistor - 1%"))
    )
    (comp (ref "R51")
      (value "49R9")
      (footprint "RESC2012X60N")
      (description "Resistor - 0.1%")
      (fields
        (field (name "TOLERANCE") "±0.1%")
        (field (name "PART NUMBER") "R0805_49R9_0.1%_0.1W_10PPM")
        (field (name "POWER") "0.1W")
        (field (name "AUTHOR") "CERN DEM JLC")
      )
      (libsource (lib "Resistors") (part "Resistor - 0.1%"))
    )
    (comp (ref "R54")
      (value "49R9")
      (footprint "RESC2012X60N")
      (description "Resistor - 0.1%")
      (fields
        (field (name "TOLERANCE") "±0.1%")
        (field (name "PART NUMBER") "R0805_49R9_0.1%_0.1W_10PPM")
        (field (name "POWER") "0.1W")
        (field (name "AUTHOR") "CERN DEM JLC")
      )
      (libsource (lib "Resistors") (part "Resistor - 0.1%"))
    )
    (comp (ref "R55")
      (value "220")
      (footprint "RESC1005X40N")
      (description "Resistor - 1%")
      (fields
        (field (name "TOLERANCE") "±1%")
        (field (name "PART NUMBER") "R0402_220R_1%_0.0625W_100PPM")
        (field (name "POWER") "0.0625W")
        (field (name "AUTHOR") "CERN DEM JLC")
      )
      (libsource (lib "Resistors") (part "Resistor - 1%"))
    )
    (comp (ref "R56")
      (value "100")
      (footprint "RESC1005X40N")
      (description "Resistor - 1%")
      (fields
        (field (name "TOLERANCE") "±1%")
        (field (name "PART NUMBER") "R0402_100R_1%_0.0625W_100PPM")
        (field (name "POWER") "0.0625W")
        (field (name "AUTHOR") "CERN DEM JLC")
      )
      (libsource (lib "Resistors") (part "Resistor - 1%"))
    )
    (comp (ref "R57")
      (value "1k")
      (footprint "RESC1005X40N")
      (description "Resistor - 1%")
      (fields
        (field (name "TOLERANCE") "±1%")
        (field (name "PART NUMBER") "R0402_1K_1%_0.0625W_100PPM")
        (field (name "POWER") "0.0625W")
        (field (name "AUTHOR") "CERN DEM JLC")
      )
      (libsource (lib "Resistors") (part "Resistor - 1%"))
    )
    (comp (ref "R58")
      (value "1k")
      (footprint "RESC1005X40N")
      (description "Resistor - 1%")
      (fields
        (field (name "TOLERANCE") "±1%")
        (field (name "PART NUMBER") "R0402_1K_1%_0.0625W_100PPM")
        (field (name "POWER") "0.0625W")
        (field (name "AUTHOR") "CERN DEM JLC")
      )
      (libsource (lib "Resistors") (part "Resistor - 1%"))
    )
    (comp (ref "R59")
      (value "1k")
      (footprint "RESC1005X40N")
      (description "Resistor - 1%")
      (fields
        (field (name "TOLERANCE") "±1%")
        (field (name "PART NUMBER") "R0402_1K_1%_0.0625W_100PPM")
        (field (name "POWER") "0.0625W")
        (field (name "AUTHOR") "CERN DEM JLC")
      )
      (libsource (lib "Resistors") (part "Resistor - 1%"))
    )
    (comp (ref "R60")
      (value "33k")
      (footprint "RESC1005X40N")
      (description "Resistor - 1%")
      (fields
        (field (name "TOLERANCE") "±1%")
        (field (name "PART NUMBER") "R0402_33K_1%_0.0625W_100PPM")
        (field (name "POWER") "0.0625W")
        (field (name "AUTHOR") "CERN DEM JLC")
      )
      (libsource (lib "Resistors") (part "Resistor - 1%"))
    )
    (comp (ref "R65")
      (value "300")
      (footprint "RESC1005X40N")
      (description "Resistor - 1%")
      (fields
        (field (name "TOLERANCE") "±1%")
        (field (name "PART NUMBER") "R0402_300R_1%_0.0625W_100PPM")
        (field (name "POWER") "0.0625W")
        (field (name "AUTHOR") "CERN DEM JLC")
      )
      (libsource (lib "Resistors") (part "Resistor - 1%"))
    )
    (comp (ref "R66")
      (value "10")
      (footprint "RESC1005X40N")
      (description "Resistor - 1%")
      (fields
        (field (name "TOLERANCE") "±1%")
        (field (name "PART NUMBER") "R0402_10R_1%_0.0625W_200PPM")
        (field (name "POWER") "0.0625W")
        (field (name "AUTHOR") "CERN DEM JLC")
      )
      (libsource (lib "Resistors") (part "Resistor - 1%"))
    )
    (comp (ref "R67")
      (value "10")
      (footprint "RESC1005X40N")
      (description "Resistor - 1%")
      (fields
        (field (name "TOLERANCE") "±1%")
        (field (name "PART NUMBER") "R0402_10R_1%_0.0625W_200PPM")
        (field (name "POWER") "0.0625W")
        (field (name "AUTHOR") "CERN DEM JLC")
      )
      (libsource (lib "Resistors") (part "Resistor - 1%"))
    )
    (comp (ref "R69")
      (value "100")
      (footprint "RESC1005X40N")
      (description "Resistor - 1%")
      (fields
        (field (name "TOLERANCE") "±1%")
        (field (name "PART NUMBER") "R0402_100R_1%_0.0625W_100PPM")
        (field (name "POWER") "0.0625W")
        (field (name "AUTHOR") "CERN DEM JLC")
      )
      (libsource (lib "Resistors") (part "Resistor - 1%"))
    )
    (comp (ref "R70")
      (value "49R9")
      (footprint "RESC2012X60N")
      (description "Resistor - 0.1%")
      (fields
        (field (name "TOLERANCE") "±0.1%")
        (field (name "PART NUMBER") "R0805_49R9_0.1%_0.1W_10PPM")
        (field (name "POWER") "0.1W")
        (field (name "AUTHOR") "CERN DEM JLC")
      )
      (libsource (lib "Resistors") (part "Resistor - 0.1%"))
    )
    (comp (ref "R73")
      (value "49R9")
      (footprint "RESC2012X60N")
      (description "Resistor - 0.1%")
      (fields
        (field (name "TOLERANCE") "±0.1%")
        (field (name "PART NUMBER") "R0805_49R9_0.1%_0.1W_10PPM")
        (field (name "POWER") "0.1W")
        (field (name "AUTHOR") "CERN DEM JLC")
      )
      (libsource (lib "Resistors") (part "Resistor - 0.1%"))
    )
    (comp (ref "R74")
      (value "220")
      (footprint "RESC1005X40N")
      (description "Resistor - 1%")
      (fields
        (field (name "TOLERANCE") "±1%")
        (field (name "PART NUMBER") "R0402_220R_1%_0.0625W_100PPM")
        (field (name "POWER") "0.0625W")
        (field (name "AUTHOR") "CERN DEM JLC")
      )
      (libsource (lib "Resistors") (part "Resistor - 1%"))
    )
    (comp (ref "R75")
      (value "100")
      (footprint "RESC1005X40N")
      (description "Resistor - 1%")
      (fields
        (field (name "TOLERANCE") "±1%")
        (field (name "PART NUMBER") "R0402_100R_1%_0.0625W_100PPM")
        (field (name "POWER") "0.0625W")
        (field (name "AUTHOR") "CERN DEM JLC")
      )
      (libsource (lib "Resistors") (part "Resistor - 1%"))
    )
    (comp (ref "R76")
      (value "1k")
      (footprint "RESC1005X40N")
      (description "Resistor - 1%")
      (fields
        (field (name "TOLERANCE") "±1%")
        (field (name "PART NUMBER") "R0402_1K_1%_0.0625W_100PPM")
        (field (name "POWER") "0.0625W")
        (field (name "AUTHOR") "CERN DEM JLC")
      )
      (libsource (lib "Resistors") (part "Resistor - 1%"))
    )
    (comp (ref "R77")
      (value "1k")
      (footprint "RESC1005X40N")
      (description "Resistor - 1%")
      (fields
        (field (name "TOLERANCE") "±1%")
        (field (name "PART NUMBER") "R0402_1K_1%_0.0625W_100PPM")
        (field (name "POWER") "0.0625W")
        (field (name "AUTHOR") "CERN DEM JLC")
      )
      (libsource (lib "Resistors") (part "Resistor - 1%"))
    )
    (comp (ref "R78")
      (value "1k")
      (footprint "RESC1005X40N")
      (description "Resistor - 1%")
      (fields
        (field (name "TOLERANCE") "±1%")
        (field (name "PART NUMBER") "R0402_1K_1%_0.0625W_100PPM")
        (field (name "POWER") "0.0625W")
        (field (name "AUTHOR") "CERN DEM JLC")
      )
      (libsource (lib "Resistors") (part "Resistor - 1%"))
    )
    (comp (ref "R79")
      (value "33k")
      (footprint "RESC1005X40N")
      (description "Resistor - 1%")
      (fields
        (field (name "TOLERANCE") "±1%")
        (field (name "PART NUMBER") "R0402_33K_1%_0.0625W_100PPM")
        (field (name "POWER") "0.0625W")
        (field (name "AUTHOR") "CERN DEM JLC")
      )
      (libsource (lib "Resistors") (part "Resistor - 1%"))
    )
    (comp (ref "R84")
      (value "10")
      (footprint "RESC1005X40N")
      (description "Resistor - 1%")
      (fields
        (field (name "TOLERANCE") "±1%")
        (field (name "PART NUMBER") "R0402_10R_1%_0.0625W_200PPM")
        (field (name "POWER") "0.0625W")
        (field (name "AUTHOR") "CERN DEM JLC")
      )
      (libsource (lib "Resistors") (part "Resistor - 1%"))
    )
    (comp (ref "R85")
      (value "300")
      (footprint "RESC1005X40N")
      (description "Resistor - 1%")
      (fields
        (field (name "TOLERANCE") "±1%")
        (field (name "PART NUMBER") "R0402_300R_1%_0.0625W_100PPM")
        (field (name "POWER") "0.0625W")
        (field (name "AUTHOR") "CERN DEM JLC")
      )
      (libsource (lib "Resistors") (part "Resistor - 1%"))
    )
  )
  (nets
    (net (code "1") (name "/CFD_OFFSET_1") (class "Default")
      (node (ref "R11") (pin "1") (pinfunction "1_1") (pintype "passive"))
    )
    (net (code "2") (name "/CFD_OFFSET_2") (class "Default")
      (node (ref "R40") (pin "1") (pinfunction "1_1") (pintype "passive"))
    )
    (net (code "3") (name "/CFD_OFFSET_3") (class "Default")
      (node (ref "R59") (pin "1") (pinfunction "1_1") (pintype "passive"))
    )
    (net (code "4") (name "/CFD_OFFSET_4") (class "Default")
      (node (ref "R78") (pin "1") (pinfunction "1_1") (pintype "passive"))
    )
    (net (code "5") (name "/IN_1") (class "Default")
      (node (ref "IC1") (pin "3") (pinfunction "IN+_3") (pintype "input"))
      (node (ref "R5") (pin "2") (pinfunction "2_2") (pintype "passive"))
    )
    (net (code "6") (name "/IN_2") (class "Default")
      (node (ref "IC6") (pin "3") (pinfunction "IN+_3") (pintype "input"))
      (node (ref "R35") (pin "2") (pinfunction "2_2") (pintype "passive"))
    )
    (net (code "7") (name "/IN_3") (class "Default")
      (node (ref "IC8") (pin "3") (pinfunction "IN+_3") (pintype "input"))
      (node (ref "R54") (pin "2") (pinfunction "2_2") (pintype "passive"))
    )
    (net (code "8") (name "/IN_4") (class "Default")
      (node (ref "IC10") (pin "3") (pinfunction "IN+_3") (pintype "input"))
      (node (ref "R73") (pin "2") (pinfunction "2_2") (pintype "passive"))
    )
    (net (code "9") (name "/OUT_1") (class "Default")
      (node (ref "IC16") (pin "1") (pinfunction "OUT_1") (pintype "output"))
      (node (ref "R1") (pin "2") (pinfunction "2_2") (pintype "passive"))
    )
    (net (code "10") (name "/OUT_2") (class "Default")
      (node (ref "IC17") (pin "1") (pinfunction "OUT_1") (pintype "output"))
      (node (ref "R16") (pin "2") (pinfunction "2_2") (pintype "passive"))
    )
    (net (code "11") (name "/OUT_3") (class "Default")
      (node (ref "IC18") (pin "1") (pinfunction "OUT_1") (pintype "output"))
      (node (ref "R25") (pin "2") (pinfunction "2_2") (pintype "passive"))
    )
    (net (code "12") (name "/OUT_4") (class "Default")
      (node (ref "IC19") (pin "1") (pinfunction "OUT_1") (pintype "output"))
      (node (ref "R43") (pin "2") (pinfunction "2_2") (pintype "passive"))
    )
    (net (code "13") (name "GND") (class "Default")
      (node (ref "C1") (pin "1") (pinfunction "1_1") (pintype "passive"))
      (node (ref "C10") (pin "1") (pinfunction "1_1") (pintype "passive"))
      (node (ref "C12") (pin "1") (pinfunction "1_1") (pintype "passive"))
      (node (ref "C13") (pin "1") (pinfunction "1_1") (pintype "passive"))
      (node (ref "C14") (pin "1") (pinfunction "1_1") (pintype "passive"))
      (node (ref "C15") (pin "1") (pinfunction "1_1") (pintype "passive"))
      (node (ref "C16") (pin "1") (pinfunction "1_1") (pintype "passive"))
      (node (ref "C17") (pin "1") (pinfunction "1_1") (pintype "passive"))
      (node (ref "C22") (pin "1") (pinfunction "1_1") (pintype "passive"))
      (node (ref "C23") (pin "1") (pinfunction "1_1") (pintype "passive"))
      (node (ref "C24") (pin "1") (pinfunction "1_1") (pintype "passive"))
      (node (ref "C25") (pin "1") (pinfunction "1_1") (pintype "passive"))
      (node (ref "C26") (pin "1") (pinfunction "1_1") (pintype "passive"))
      (node (ref "C29") (pin "1") (pinfunction "1_1") (pintype "passive"))
      (node (ref "C30") (pin "1") (pinfunction "1_1") (pintype "passive"))
      (node (ref "C31") (pin "1") (pinfunction "1_1") (pintype "passive"))
      (node (ref "C32") (pin "1") (pinfunction "1_1") (pintype "passive"))
      (node (ref "C33") (pin "1") (pinfunction "1_1") (pintype "passive"))
      (node (ref "C34") (pin "1") (pinfunction "1_1") (pintype "passive"))
      (node (ref "C35") (pin "1") (pinfunction "1_1") (pintype "passive"))
      (node (ref "C36") (pin "1") (pinfunction "1_1") (pintype "passive"))
      (node (ref "C5") (pin "1") (pinfunction "1_1") (pintype "passive"))
      (node (ref "C6") (pin "1") (pinfunction "1_1") (pintype "passive"))
      (node (ref "C63") (pin "1") (pinfunction "1_1") (pintype "passive"))
      (node (ref "C64") (pin "1") (pinfunction "1_1") (pintype "passive"))
      (node (ref "C65") (pin "1") (pinfunction "1_1") (pintype "passive"))
      (node (ref "C66") (pin "1") (pinfunction "1_1") (pintype "passive"))
      (node (ref "C67") (pin "1") (pinfunction "1_1") (pintype "passive"))
      (node (ref "C68") (pin "1") (pinfunction "1_1") (pintype "passive"))
      (node (ref "C69") (pin "1") (pinfunction "1_1") (pintype "passive"))
      (node (ref "C7") (pin "1") (pinfunction "1_1") (pintype "passive"))
      (node (ref "C70") (pin "1") (pinfunction "1_1") (pintype "passive"))
      (node (ref "IC1") (pin "9") (pinfunction "EP_9") (pintype "passive"))
      (node (ref "IC10") (pin "9") (pinfunction "EP_9") (pintype "passive"))
      (node (ref "IC16") (pin "3") (pinfunction "IN+_3") (pintype "input"))
      (node (ref "IC17") (pin "3") (pinfunction "IN+_3") (pintype "input"))
      (node (ref "IC18") (pin "3") (pinfunction "IN+_3") (pintype "input"))
      (node (ref "IC19") (pin "3") (pinfunction "IN+_3") (pintype "input"))
      (node (ref "IC6") (pin "9") (pinfunction "EP_9") (pintype "passive"))
      (node (ref "IC8") (pin "9") (pinfunction "EP_9") (pintype "passive"))
      (node (ref "J1") (pin "2") (pinfunction "2_2") (pintype "bidirectional"))
      (node (ref "J17") (pin "2") (pinfunction "2_2") (pintype "bidirectional"))
      (node (ref "J18") (pin "2") (pinfunction "2_2") (pintype "bidirectional"))
      (node (ref "J19") (pin "2") (pinfunction "2_2") (pintype "bidirectional"))
      (node (ref "J2") (pin "2") (pinfunction "2_2") (pintype "bidirectional"))
      (node (ref "J20") (pin "2") (pinfunction "2_2") (pintype "bidirectional"))
      (node (ref "J21") (pin "2") (pinfunction "2_2") (pintype "bidirectional"))
      (node (ref "J22") (pin "2") (pinfunction "2_2") (pintype "bidirectional"))
      (node (ref "R13") (pin "1") (pinfunction "1_1") (pintype "passive"))
      (node (ref "R14") (pin "2") (pinfunction "2_2") (pintype "passive"))
      (node (ref "R15") (pin "1") (pinfunction "1_1") (pintype "passive"))
      (node (ref "R18") (pin "1") (pinfunction "1_1") (pintype "passive"))
      (node (ref "R19") (pin "1") (pinfunction "1_1") (pintype "passive"))
      (node (ref "R29") (pin "1") (pinfunction "1_1") (pintype "passive"))
      (node (ref "R31") (pin "1") (pinfunction "1_1") (pintype "passive"))
      (node (ref "R35") (pin "1") (pinfunction "1_1") (pintype "passive"))
      (node (ref "R36") (pin "1") (pinfunction "1_1") (pintype "passive"))
      (node (ref "R39") (pin "2") (pinfunction "2_2") (pintype "passive"))
      (node (ref "R4") (pin "1") (pinfunction "1_1") (pintype "passive"))
      (node (ref "R41") (pin "1") (pinfunction "1_1") (pintype "passive"))
      (node (ref "R42") (pin "1") (pinfunction "1_1") (pintype "passive"))
      (node (ref "R45") (pin "1") (pinfunction "1_1") (pintype "passive"))
      (node (ref "R46") (pin "1") (pinfunction "1_1") (pintype "passive"))
      (node (ref "R49") (pin "1") (pinfunction "1_1") (pintype "passive"))
      (node (ref "R5") (pin "1") (pinfunction "1_1") (pintype "passive"))
      (node (ref "R51") (pin "1") (pinfunction "1_1") (pintype "passive"))
      (node (ref "R54") (pin "1") (pinfunction "1_1") (pintype "passive"))
      (node (ref "R55") (pin "1") (pinfunction "1_1") (pintype "passive"))
      (node (ref "R58") (pin "2") (pinfunction "2_2") (pintype "passive"))
      (node (ref "R6") (pin "1") (pinfunction "1_1") (pintype "passive"))
      (node (ref "R60") (pin "1") (pinfunction "1_1") (pintype "passive"))
      (node (ref "R66") (pin "1") (pinfunction "1_1") (pintype "passive"))
      (node (ref "R70") (pin "1") (pinfunction "1_1") (pintype "passive"))
      (node (ref "R73") (pin "1") (pinfunction "1_1") (pintype "passive"))
      (node (ref "R74") (pin "1") (pinfunction "1_1") (pintype "passive"))
      (node (ref "R77") (pin "2") (pinfunction "2_2") (pintype "passive"))
      (node (ref "R79") (pin "1") (pinfunction "1_1") (pintype "passive"))
      (node (ref "R8") (pin "1") (pinfunction "1_1") (pintype "passive"))
      (node (ref "R84") (pin "1") (pinfunction "1_1") (pintype "passive"))
      (node (ref "R9") (pin "1") (pinfunction "1_1") (pintype "passive"))
    )
    (net (code "14") (name "N5V0A") (class "Default")
      (node (ref "C13") (pin "2") (pinfunction "2_2") (pintype "passive"))
      (node (ref "C17") (pin "2") (pinfunction "2_2") (pintype "passive"))
      (node (ref "C25") (pin "2") (pinfunction "2_2") (pintype "passive"))
      (node (ref "C30") (pin "2") (pinfunction "2_2") (pintype "passive"))
      (node (ref "C32") (pin "2") (pinfunction "2_2") (pintype "passive"))
      (node (ref "C34") (pin "2") (pinfunction "2_2") (pintype "passive"))
      (node (ref "C36") (pin "2") (pinfunction "2_2") (pintype "passive"))
      (node (ref "C6") (pin "2") (pinfunction "2_2") (pintype "passive"))
      (node (ref "C64") (pin "2") (pinfunction "2_2") (pintype "passive"))
      (node (ref "C66") (pin "2") (pinfunction "2_2") (pintype "passive"))
      (node (ref "C68") (pin "2") (pinfunction "2_2") (pintype "passive"))
      (node (ref "C70") (pin "2") (pinfunction "2_2") (pintype "passive"))
      (node (ref "IC1") (pin "4") (pinfunction "V-_4") (pintype "power_in"))
      (node (ref "IC10") (pin "4") (pinfunction "V-_4") (pintype "power_in"))
      (node (ref "IC16") (pin "2") (pinfunction "V-_2") (pintype "power_in"))
      (node (ref "IC17") (pin "2") (pinfunction "V-_2") (pintype "power_in"))
      (node (ref "IC18") (pin "2") (pinfunction "V-_2") (pintype "power_in"))
      (node (ref "IC19") (pin "2") (pinfunction "V-_2") (pintype "power_in"))
      (node (ref "IC2") (pin "15") (pinfunction "VEE_15") (pintype "power_in"))
      (node (ref "IC2") (pin "6") (pinfunction "VEE_6") (pintype "power_in"))
      (node (ref "IC6") (pin "4") (pinfunction "V-_4") (pintype "power_in"))
      (node (ref "IC8") (pin "4") (pinfunction "V-_4") (pintype "power_in"))
      (node (ref "IC9") (pin "15") (pinfunction "VEE_15") (pintype "power_in"))
      (node (ref "IC9") (pin "6") (pinfunction "VEE_6") (pintype "power_in"))
    )
    (net (code "15") (name "Net-(C1-Pad2)") (class "Default")
      (node (ref "C1") (pin "2") (pinfunction "2_2") (pintype "passive"))
      (node (ref "C5") (pin "2") (pinfunction "2_2") (pintype "passive"))
      (node (ref "R10") (pin "1") (pinfunction "1_1") (pintype "passive"))
      (node (ref "R11") (pin "2") (pinfunction "2_2") (pintype "passive"))
      (node (ref "R13") (pin "2") (pinfunction "2_2") (pintype "passive"))
    )
    (net (code "16") (name "Net-(C10-Pad2)") (class "Default")
      (node (ref "C10") (pin "2") (pinfunction "2_2") (pintype "passive"))
      (node (ref "C12") (pin "2") (pinfunction "2_2") (pintype "passive"))
      (node (ref "R37") (pin "1") (pinfunction "1_1") (pintype "passive"))
      (node (ref "R40") (pin "2") (pinfunction "2_2") (pintype "passive"))
      (node (ref "R46") (pin "2") (pinfunction "2_2") (pintype "passive"))
    )
    (net (code "17") (name "Net-(C15-Pad2)") (class "Default")
      (node (ref "C15") (pin "2") (pinfunction "2_2") (pintype "passive"))
      (node (ref "C16") (pin "2") (pinfunction "2_2") (pintype "passive"))
      (node (ref "R56") (pin "1") (pinfunction "1_1") (pintype "passive"))
      (node (ref "R59") (pin "2") (pinfunction "2_2") (pintype "passive"))
      (node (ref "R66") (pin "2") (pinfunction "2_2") (pintype "passive"))
    )
    (net (code "18") (name "Net-(C23-Pad2)") (class "Default")
      (node (ref "C23") (pin "2") (pinfunction "2_2") (pintype "passive"))
      (node (ref "C24") (pin "2") (pinfunction "2_2") (pintype "passive"))
      (node (ref "R75") (pin "1") (pinfunction "1_1") (pintype "passive"))
      (node (ref "R78") (pin "2") (pinfunction "2_2") (pintype "passive"))
      (node (ref "R84") (pin "2") (pinfunction "2_2") (pintype "passive"))
    )
    (net (code "19") (name "Net-(C58-Pad1)") (class "Default")
      (node (ref "C58") (pin "1") (pinfunction "1_1") (pintype "passive"))
      (node (ref "R7") (pin "1") (pinfunction "1_1") (pintype "passive"))
    )
    (net (code "20") (name "Net-(C59-Pad1)") (class "Default")
      (node (ref "C59") (pin "1") (pinfunction "1_1") (pintype "passive"))
      (node (ref "R17") (pin "1") (pinfunction "1_1") (pintype "passive"))
    )
    (net (code "21") (name "Net-(C60-Pad1)") (class "Default")
      (node (ref "C60") (pin "1") (pinfunction "1_1") (pintype "passive"))
      (node (ref "R30") (pin "1") (pinfunction "1_1") (pintype "passive"))
    )
    (net (code "22") (name "Net-(C62-Pad1)") (class "Default")
      (node (ref "C62") (pin "1") (pinfunction "1_1") (pintype "passive"))
      (node (ref "R44") (pin "1") (pinfunction "1_1") (pintype "passive"))
    )
    (net (code "23") (name "Net-(IC1-IN-)") (class "Default")
      (node (ref "IC1") (pin "2") (pinfunction "IN-_2") (pintype "input"))
      (node (ref "R6") (pin "2") (pinfunction "2_2") (pintype "passive"))
      (node (ref "R85") (pin "1") (pinfunction "1_1") (pintype "passive"))
    )
    (net (code "24") (name "Net-(IC1-OUT)") (class "Default")
      (node (ref "IC1") (pin "6") (pinfunction "OUT_6") (pintype "output"))
      (node (ref "R2") (pin "1") (pinfunction "1_1") (pintype "passive"))
      (node (ref "R85") (pin "2") (pinfunction "2_2") (pintype "passive"))
    )
    (net (code "25") (name "Net-(IC2A-HYSA)") (class "Default")
      (node (ref "IC2") (pin "8") (pinfunction "HYSA_8") (pintype "input"))
      (node (ref "R15") (pin "2") (pinfunction "2_2") (pintype "passive"))
    )
    (net (code "26") (name "Net-(IC2A-INA+)") (class "Default")
      (node (ref "IC2") (pin "10") (pinfunction "INA+_10") (pintype "input"))
      (node (ref "R10") (pin "2") (pinfunction "2_2") (pintype "passive"))
      (node (ref "R3") (pin "1") (pinfunction "1_1") (pintype "passive"))
    )
    (net (code "27") (name "Net-(IC2A-INA-)") (class "Default")
      (node (ref "IC2") (pin "9") (pinfunction "INA-_9") (pintype "input"))
      (node (ref "J2") (pin "1") (pinfunction "1_1") (pintype "bidirectional"))
      (node (ref "R4") (pin "2") (pinfunction "2_2") (pintype "passive"))
    )
    (net (code "28") (name "Net-(IC2A-LEA)") (class "Default")
      (node (ref "IC2") (pin "4") (pinfunction "LEA_4") (pintype "input"))
      (node (ref "R12") (pin "1") (pinfunction "1_1") (pintype "passive"))
    )
    (net (code "29") (name "Net-(IC2A-QA)") (class "Default")
      (node (ref "C58") (pin "2") (pinfunction "2_2") (pintype "passive"))
      (node (ref "IC2") (pin "1") (pinfunction "QA_1") (pintype "output"))
      (node (ref "R9") (pin "2") (pinfunction "2_2") (pintype "passive"))
    )
    (net (code "30") (name "Net-(IC2A-~{LEA})") (class "Default")
      (node (ref "IC2") (pin "5") (pinfunction "~{LEA}_5") (pintype "input"))
      (node (ref "R14") (pin "1") (pinfunction "1_1") (pintype "passive"))
    )
    (net (code "31") (name "Net-(IC2A-~{QA})") (class "Default")
      (node (ref "IC2") (pin "2") (pinfunction "~{QA}_2") (pintype "output"))
      (node (ref "R8") (pin "2") (pinfunction "2_2") (pintype "passive"))
    )
    (net (code "32") (name "Net-(IC2B-HYSB)") (class "Default")
      (node (ref "IC2") (pin "13") (pinfunction "HYSB_13") (pintype "input"))
      (node (ref "R41") (pin "2") (pinfunction "2_2") (pintype "passive"))
    )
    (net (code "33") (name "Net-(IC2B-INB+)") (class "Default")
      (node (ref "IC2") (pin "11") (pinfunction "INB+_11") (pintype "input"))
      (node (ref "R28") (pin "1") (pinfunction "1_1") (pintype "passive"))
      (node (ref "R37") (pin "2") (pinfunction "2_2") (pintype "passive"))
    )
    (net (code "34") (name "Net-(IC2B-INB-)") (class "Default")
      (node (ref "IC2") (pin "12") (pinfunction "INB-_12") (pintype "input"))
      (node (ref "J18") (pin "1") (pinfunction "1_1") (pintype "bidirectional"))
      (node (ref "R29") (pin "2") (pinfunction "2_2") (pintype "passive"))
    )
    (net (code "35") (name "Net-(IC2B-LEB)") (class "Default")
      (node (ref "IC2") (pin "17") (pinfunction "LEB_17") (pintype "input"))
      (node (ref "R38") (pin "1") (pinfunction "1_1") (pintype "passive"))
    )
    (net (code "36") (name "Net-(IC2B-QB)") (class "Default")
      (node (ref "C59") (pin "2") (pinfunction "2_2") (pintype "passive"))
      (node (ref "IC2") (pin "20") (pinfunction "QB_20") (pintype "output"))
      (node (ref "R19") (pin "2") (pinfunction "2_2") (pintype "passive"))
    )
    (net (code "37") (name "Net-(IC2B-~{LEB})") (class "Default")
      (node (ref "IC2") (pin "16") (pinfunction "~{LEB}_16") (pintype "input"))
      (node (ref "R39") (pin "1") (pinfunction "1_1") (pintype "passive"))
    )
    (net (code "38") (name "Net-(IC2B-~{QB})") (class "Default")
      (node (ref "IC2") (pin "19") (pinfunction "~{QB}_19") (pintype "output"))
      (node (ref "R18") (pin "2") (pinfunction "2_2") (pintype "passive"))
    )
    (net (code "39") (name "Net-(IC6-IN-)") (class "Default")
      (node (ref "IC6") (pin "2") (pinfunction "IN-_2") (pintype "input"))
      (node (ref "R23") (pin "1") (pinfunction "1_1") (pintype "passive"))
      (node (ref "R36") (pin "2") (pinfunction "2_2") (pintype "passive"))
    )
    (net (code "40") (name "Net-(IC6-OUT)") (class "Default")
      (node (ref "IC6") (pin "6") (pinfunction "OUT_6") (pintype "output"))
      (node (ref "R23") (pin "2") (pinfunction "2_2") (pintype "passive"))
      (node (ref "R24") (pin "1") (pinfunction "1_1") (pintype "passive"))
    )
    (net (code "41") (name "Net-(IC8-IN-)") (class "Default")
      (node (ref "IC8") (pin "2") (pinfunction "IN-_2") (pintype "input"))
      (node (ref "R47") (pin "1") (pinfunction "1_1") (pintype "passive"))
      (node (ref "R55") (pin "2") (pinfunction "2_2") (pintype "passive"))
    )
    (net (code "42") (name "Net-(IC8-OUT)") (class "Default")
      (node (ref "IC8") (pin "6") (pinfunction "OUT_6") (pintype "output"))
      (node (ref "R47") (pin "2") (pinfunction "2_2") (pintype "passive"))
      (node (ref "R48") (pin "1") (pinfunction "1_1") (pintype "passive"))
    )
    (net (code "43") (name "Net-(IC9A-HYSA)") (class "Default")
      (node (ref "IC9") (pin "8") (pinfunction "HYSA_8") (pintype "input"))
      (node (ref "R60") (pin "2") (pinfunction "2_2") (pintype "passive"))
    )
    (net (code "44") (name "Net-(IC9A-INA+)") (class "Default")
      (node (ref "IC9") (pin "10") (pinfunction "INA+_10") (pintype "input"))
      (node (ref "R50") (pin "1") (pinfunction "1_1") (pintype "passive"))
      (node (ref "R56") (pin "2") (pinfunction "2_2") (pintype "passive"))
    )
    (net (code "45") (name "Net-(IC9A-INA-)") (class "Default")
      (node (ref "IC9") (pin "9") (pinfunction "INA-_9") (pintype "input"))
      (node (ref "J20") (pin "1") (pinfunction "1_1") (pintype "bidirectional"))
      (node (ref "R51") (pin "2") (pinfunction "2_2") (pintype "passive"))
    )
    (net (code "46") (name "Net-(IC9A-LEA)") (class "Default")
      (node (ref "IC9") (pin "4") (pinfunction "LEA_4") (pintype "input"))
      (node (ref "R57") (pin "1") (pinfunction "1_1") (pintype "passive"))
    )
    (net (code "47") (name "Net-(IC9A-QA)") (class "Default")
      (node (ref "C60") (pin "2") (pinfunction "2_2") (pintype "passive"))
      (node (ref "IC9") (pin "1") (pinfunction "QA_1") (pintype "output"))
      (node (ref "R42") (pin "2") (pinfunction "2_2") (pintype "passive"))
    )
    (net (code "48") (name "Net-(IC9A-~{LEA})") (class "Default")
      (node (ref "IC9") (pin "5") (pinfunction "~{LEA}_5") (pintype "input"))
      (node (ref "R58") (pin "1") (pinfunction "1_1") (pintype "passive"))
    )
    (net (code "49") (name "Net-(IC9A-~{QA})") (class "Default")
      (node (ref "IC9") (pin "2") (pinfunction "~{QA}_2") (pintype "output"))
      (node (ref "R31") (pin "2") (pinfunction "2_2") (pintype "passive"))
    )
    (net (code "50") (name "Net-(IC9B-HYSB)") (class "Default")
      (node (ref "IC9") (pin "13") (pinfunction "HYSB_13") (pintype "input"))
      (node (ref "R79") (pin "2") (pinfunction "2_2") (pintype "passive"))
    )
    (net (code "51") (name "Net-(IC9B-INB+)") (class "Default")
      (node (ref "IC9") (pin "11") (pinfunction "INB+_11") (pintype "input"))
      (node (ref "R69") (pin "1") (pinfunction "1_1") (pintype "passive"))
      (node (ref "R75") (pin "2") (pinfunction "2_2") (pintype "passive"))
    )
    (net (code "52") (name "Net-(IC9B-INB-)") (class "Default")
      (node (ref "IC9") (pin "12") (pinfunction "INB-_12") (pintype "input"))
      (node (ref "J22") (pin "1") (pinfunction "1_1") (pintype "bidirectional"))
      (node (ref "R70") (pin "2") (pinfunction "2_2") (pintype "passive"))
    )
    (net (code "53") (name "Net-(IC9B-LEB)") (class "Default")
      (node (ref "IC9") (pin "17") (pinfunction "LEB_17") (pintype "input"))
      (node (ref "R76") (pin "1") (pinfunction "1_1") (pintype "passive"))
    )
    (net (code "54") (name "Net-(IC9B-QB)") (class "Default")
      (node (ref "C62") (pin "2") (pinfunction "2_2") (pintype "passive"))
      (node (ref "IC9") (pin "20") (pinfunction "QB_20") (pintype "output"))
      (node (ref "R49") (pin "2") (pinfunction "2_2") (pintype "passive"))
    )
    (net (code "55") (name "Net-(IC9B-~{LEB})") (class "Default")
      (node (ref "IC9") (pin "16") (pinfunction "~{LEB}_16") (pintype "input"))
      (node (ref "R77") (pin "1") (pinfunction "1_1") (pintype "passive"))
    )
    (net (code "56") (name "Net-(IC9B-~{QB})") (class "Default")
      (node (ref "IC9") (pin "19") (pinfunction "~{QB}_19") (pintype "output"))
      (node (ref "R45") (pin "2") (pinfunction "2_2") (pintype "passive"))
    )
    (net (code "57") (name "Net-(IC10-IN-)") (class "Default")
      (node (ref "IC10") (pin "2") (pinfunction "IN-_2") (pintype "input"))
      (node (ref "R65") (pin "1") (pinfunction "1_1") (pintype "passive"))
      (node (ref "R74") (pin "2") (pinfunction "2_2") (pintype "passive"))
    )
    (net (code "58") (name "Net-(IC10-OUT)") (class "Default")
      (node (ref "IC10") (pin "6") (pinfunction "OUT_6") (pintype "output"))
      (node (ref "R65") (pin "2") (pinfunction "2_2") (pintype "passive"))
      (node (ref "R67") (pin "1") (pinfunction "1_1") (pintype "passive"))
    )
    (net (code "59") (name "Net-(IC16-IN-)") (class "Default")
      (node (ref "IC16") (pin "4") (pinfunction "IN-_4") (pintype "input"))
      (node (ref "R1") (pin "1") (pinfunction "1_1") (pintype "passive"))
      (node (ref "R7") (pin "2") (pinfunction "2_2") (pintype "passive"))
    )
    (net (code "60") (name "Net-(IC17-IN-)") (class "Default")
      (node (ref "IC17") (pin "4") (pinfunction "IN-_4") (pintype "input"))
      (node (ref "R16") (pin "1") (pinfunction "1_1") (pintype "passive"))
      (node (ref "R17") (pin "2") (pinfunction "2_2") (pintype "passive"))
    )
    (net (code "61") (name "Net-(IC18-IN-)") (class "Default")
      (node (ref "IC18") (pin "4") (pinfunction "IN-_4") (pintype "input"))
      (node (ref "R25") (pin "1") (pinfunction "1_1") (pintype "passive"))
      (node (ref "R30") (pin "2") (pinfunction "2_2") (pintype "passive"))
    )
    (net (code "62") (name "Net-(IC19-IN-)") (class "Default")
      (node (ref "IC19") (pin "4") (pinfunction "IN-_4") (pintype "input"))
      (node (ref "R43") (pin "1") (pinfunction "1_1") (pintype "passive"))
      (node (ref "R44") (pin "2") (pinfunction "2_2") (pintype "passive"))
    )
    (net (code "63") (name "Net-(J1-Pad1)") (class "Default")
      (node (ref "J1") (pin "1") (pinfunction "1_1") (pintype "bidirectional"))
      (node (ref "R2") (pin "2") (pinfunction "2_2") (pintype "passive"))
      (node (ref "R3") (pin "2") (pinfunction "2_2") (pintype "passive"))
    )
    (net (code "64") (name "Net-(J17-Pad1)") (class "Default")
      (node (ref "J17") (pin "1") (pinfunction "1_1") (pintype "bidirectional"))
      (node (ref "R24") (pin "2") (pinfunction "2_2") (pintype "passive"))
      (node (ref "R28") (pin "2") (pinfunction "2_2") (pintype "passive"))
    )
    (net (code "65") (name "Net-(J19-Pad1)") (class "Default")
      (node (ref "J19") (pin "1") (pinfunction "1_1") (pintype "bidirectional"))
      (node (ref "R48") (pin "2") (pinfunction "2_2") (pintype "passive"))
      (node (ref "R50") (pin "2") (pinfunction "2_2") (pintype "passive"))
    )
    (net (code "66") (name "Net-(J21-Pad1)") (class "Default")
      (node (ref "J21") (pin "1") (pinfunction "1_1") (pintype "bidirectional"))
      (node (ref "R67") (pin "2") (pinfunction "2_2") (pintype "passive"))
      (node (ref "R69") (pin "2") (pinfunction "2_2") (pintype "passive"))
    )
    (net (code "67") (name "P5V0A") (class "Default")
      (node (ref "C14") (pin "2") (pinfunction "2_2") (pintype "passive"))
      (node (ref "C22") (pin "2") (pinfunction "2_2") (pintype "passive"))
      (node (ref "C26") (pin "2") (pinfunction "2_2") (pintype "passive"))
      (node (ref "C29") (pin "2") (pinfunction "2_2") (pintype "passive"))
      (node (ref "C31") (pin "2") (pinfunction "2_2") (pintype "passive"))
      (node (ref "C33") (pin "2") (pinfunction "2_2") (pintype "passive"))
      (node (ref "C35") (pin "2") (pinfunction "2_2") (pintype "passive"))
      (node (ref "C63") (pin "2") (pinfunction "2_2") (pintype "passive"))
      (node (ref "C65") (pin "2") (pinfunction "2_2") (pintype "passive"))
      (node (ref "C67") (pin "2") (pinfunction "2_2") (pintype "passive"))
      (node (ref "C69") (pin "2") (pinfunction "2_2") (pintype "passive"))
      (node (ref "C7") (pin "2") (pinfunction "2_2") (pintype "passive"))
      (node (ref "IC1") (pin "7") (pinfunction "V+_7") (pintype "power_in"))
      (node (ref "IC10") (pin "7") (pinfunction "V+_7") (pintype "power_in"))
      (node (ref "IC16") (pin "5") (pinfunction "V+_5") (pintype "power_in"))
      (node (ref "IC17") (pin "5") (pinfunction "V+_5") (pintype "power_in"))
      (node (ref "IC18") (pin "5") (pinfunction "V+_5") (pintype "power_in"))
      (node (ref "IC19") (pin "5") (pinfunction "V+_5") (pintype "power_in"))
      (node (ref "IC2") (pin "14") (pinfunction "VCC_14") (pintype "power_in"))
      (node (ref "IC2") (pin "18") (pinfunction "VCCOB_18") (pintype "power_in"))
      (node (ref "IC2") (pin "3") (pinfunction "VCCOA_3") (pintype "power_in"))
      (node (ref "IC2") (pin "7") (pinfunction "VCC_7") (pintype "power_in"))
      (node (ref "IC6") (pin "7") (pinfunction "V+_7") (pintype "power_in"))
      (node (ref "IC8") (pin "7") (pinfunction "V+_7") (pintype "power_in"))
      (node (ref "IC9") (pin "14") (pinfunction "VCC_14") (pintype "power_in"))
      (node (ref "IC9") (pin "18") (pinfunction "VCCOB_18") (pintype "power_in"))
      (node (ref "IC9") (pin "3") (pinfunction "VCCOA_3") (pintype "power_in"))
      (node (ref "IC9") (pin "7") (pinfunction "VCC_7") (pintype "power_in"))
      (node (ref "R12") (pin "2") (pinfunction "2_2") (pintype "passive"))
      (node (ref "R38") (pin "2") (pinfunction "2_2") (pintype "passive"))
      (node (ref "R57") (pin "2") (pinfunction "2_2") (pintype "passive"))
      (node (ref "R76") (pin "2") (pinfunction "2_2") (pintype "passive"))
    )
    (net (code "68") (name "unconnected-(IC1-NC-Pad1)") (class "Default")
      (node (ref "IC1") (pin "1") (pinfunction "NC_1") (pintype "passive"))
    )
    (net (code "69") (name "unconnected-(IC1-NC-Pad5)") (class "Default")
      (node (ref "IC1") (pin "5") (pinfunction "NC_5") (pintype "passive"))
    )
    (net (code "70") (name "unconnected-(IC1-NC-Pad8)") (class "Default")
      (node (ref "IC1") (pin "8") (pinfunction "NC_8") (pintype "passive"))
    )
    (net (code "71") (name "unconnected-(IC6-NC-Pad1)") (class "Default")
      (node (ref "IC6") (pin "1") (pinfunction "NC_1") (pintype "passive"))
    )
    (net (code "72") (name "unconnected-(IC6-NC-Pad5)") (class "Default")
      (node (ref "IC6") (pin "5") (pinfunction "NC_5") (pintype "passive"))
    )
    (net (code "73") (name "unconnected-(IC6-NC-Pad8)") (class "Default")
      (node (ref "IC6") (pin "8") (pinfunction "NC_8") (pintype "passive"))
    )
    (net (code "74") (name "unconnected-(IC8-NC-Pad1)") (class "Default")
      (node (ref "IC8") (pin "1") (pinfunction "NC_1") (pintype "passive"))
    )
    (net (code "75") (name "unconnected-(IC8-NC-Pad5)") (class "Default")
      (node (ref "IC8") (pin "5") (pinfunction "NC_5") (pintype "passive"))
    )
    (net (code "76") (name "unconnected-(IC8-NC-Pad8)") (class "Default")
      (node (ref "IC8") (pin "8") (pinfunction "NC_8") (pintype "passive"))
    )
    (net (code "77") (name "unconnected-(IC10-NC-Pad1)") (class "Default")
      (node (ref "IC10") (pin "1") (pinfunction "NC_1") (pintype "passive"))
    )
    (net (code "78") (name "unconnected-(IC10-NC-Pad5)") (class "Default")
      (node (ref "IC10") (pin "5") (pinfunction "NC_5") (pintype "passive"))
    )
    (net (code "79") (name "unconnected-(IC10-NC-Pad8)") (class "Default")
      (node (ref "IC10") (pin "8") (pinfunction "NC_8") (pintype "passive"))
    )
  )
)
